# BB-DS.net
KiCad netlist of a schematic drawn in EAGLE
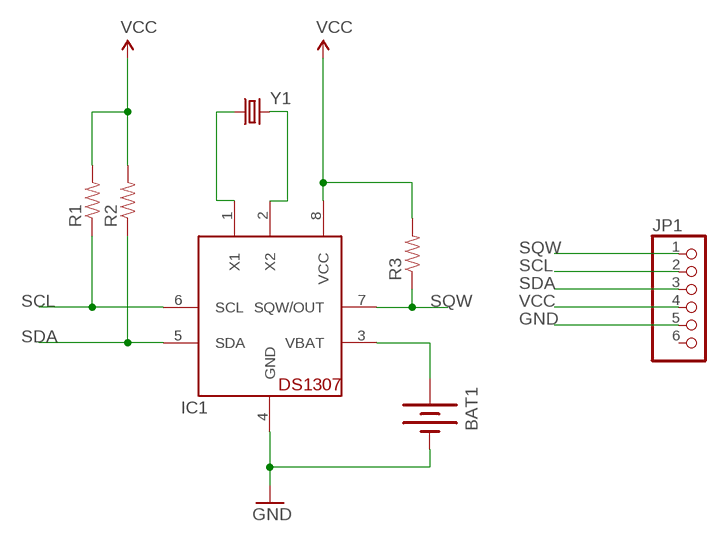
[diagram p0: schematic, sheet 1]

(export (version "E")
  (design (tool "Eeschema 10.0.6"))
  (components
    (comp (ref "BAT1")
      (value "BATTERY20PTH")
      (footprint "eagle-import:BATTCOM_20MM_PTH")
      (libsource (lib "eagle-import") (part "BATTERY20PTH"))
    )
    (comp (ref "IC1")
      (value "DS1307")
      (footprint "eagle-import:DIL08")
      (libsource (lib "eagle-import") (part "DS1307"))
    )
    (comp (ref "JP1")
      (value "PINHD-1X6B")
      (footprint "eagle-import:1X06-BIG")
      (libsource (lib "eagle-import") (part "PINHD-1X6B"))
    )
    (comp (ref "R1")
      (value "RESISTORPTH-1/4W")
      (footprint "eagle-import:AXIAL-0.4")
      (libsource (lib "eagle-import") (part "RESISTORPTH-1/4W"))
    )
    (comp (ref "R2")
      (value "RESISTORPTH-1/4W")
      (footprint "eagle-import:AXIAL-0.4")
      (libsource (lib "eagle-import") (part "RESISTORPTH-1/4W"))
    )
    (comp (ref "R3")
      (value "RESISTORPTH-1/4W")
      (footprint "eagle-import:AXIAL-0.4")
      (libsource (lib "eagle-import") (part "RESISTORPTH-1/4W"))
    )
    (comp (ref "Y1")
      (value "CRYSTALTC26H_EZ")
      (footprint "eagle-import:TC26HEZ")
      (libsource (lib "eagle-import") (part "CRYSTALTC26H_EZ"))
    )
  )
  (nets
    (net (code "1") (name "/SCL") (class "Default")
      (node (ref "IC1") (pin "6") (pinfunction "SCL_6") (pintype "bidirectional"))
      (node (ref "JP1") (pin "2") (pinfunction "2_2") (pintype "passive"))
      (node (ref "R1") (pin "P$1") (pinfunction "1_P$1") (pintype "passive"))
    )
    (net (code "2") (name "/SDA") (class "Default")
      (node (ref "IC1") (pin "5") (pinfunction "SDA_5") (pintype "bidirectional"))
      (node (ref "JP1") (pin "3") (pinfunction "3_3") (pintype "passive"))
      (node (ref "R2") (pin "P$1") (pinfunction "1_P$1") (pintype "passive"))
    )
    (net (code "3") (name "/SQW") (class "Default")
      (node (ref "IC1") (pin "7") (pinfunction "SQW/OUT_7") (pintype "bidirectional"))
      (node (ref "JP1") (pin "1") (pinfunction "1_1") (pintype "passive"))
      (node (ref "R3") (pin "P$1") (pinfunction "1_P$1") (pintype "passive"))
    )
    (net (code "4") (name "GND") (class "Default")
      (node (ref "BAT1") (pin "2") (pinfunction "-_2") (pintype "power_in"))
      (node (ref "IC1") (pin "4") (pinfunction "GND_4") (pintype "power_in"))
      (node (ref "JP1") (pin "5") (pinfunction "5_5") (pintype "passive"))
    )
    (net (code "5") (name "Net-(BAT1-+)") (class "Default")
      (node (ref "BAT1") (pin "1") (pinfunction "+_1") (pintype "power_in"))
      (node (ref "IC1") (pin "3") (pinfunction "VBAT_3") (pintype "power_in"))
    )
    (net (code "6") (name "Net-(IC1-X1)") (class "Default")
      (node (ref "IC1") (pin "1") (pinfunction "X1_1") (pintype "passive"))
      (node (ref "Y1") (pin "1") (pinfunction "1_1") (pintype "passive"))
    )
    (net (code "7") (name "Net-(IC1-X2)") (class "Default")
      (node (ref "IC1") (pin "2") (pinfunction "X2_2") (pintype "passive"))
      (node (ref "Y1") (pin "2") (pinfunction "2_2") (pintype "passive"))
    )
    (net (code "8") (name "VCC") (class "Default")
      (node (ref "IC1") (pin "8") (pinfunction "VCC_8") (pintype "power_in"))
      (node (ref "JP1") (pin "4") (pinfunction "4_4") (pintype "passive"))
      (node (ref "R1") (pin "P$2") (pinfunction "2_P$2") (pintype "passive"))
      (node (ref "R2") (pin "P$2") (pinfunction "2_P$2") (pintype "passive"))
      (node (ref "R3") (pin "P$2") (pinfunction "2_P$2") (pintype "passive"))
    )
    (net (code "9") (name "unconnected-(JP1-Pad6)") (class "Default")
      (node (ref "JP1") (pin "6") (pinfunction "6_6") (pintype "passive"))
    )
  )
)
